# board_schematic.net
KiCad netlist of a schematic drawn in Altium Designer
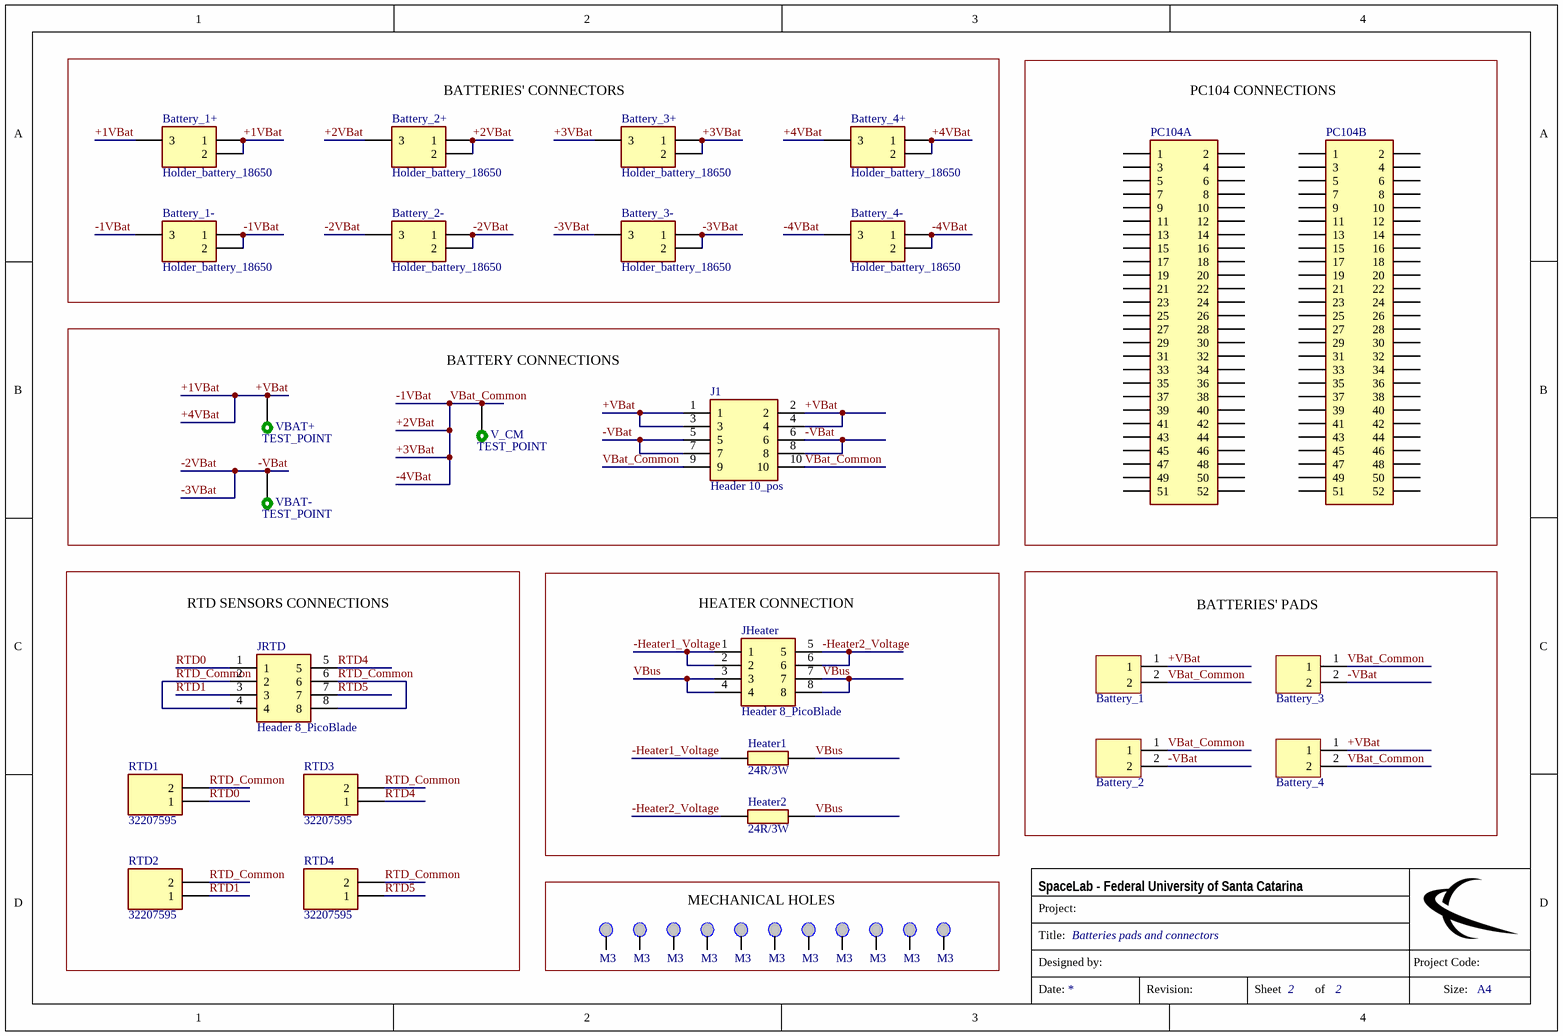
[diagram p0: board_schematic.schdoc]

(export (version "E")
  (design (tool "Eeschema 10.0.6"))
  (components
    (comp (ref "Battery_1")
      (value "BATTERY")
      (footprint "BATTERY")
      (description "Battery Pads")
      (libsource (lib "Battery_V2") (part "BATTERY"))
    )
    (comp (ref "Battery_1+")
      (value "Holder_battery_18650")
      (footprint "54")
      (description "Cylindrical Battery Contacts, Clips, Holders & Springs 16-19mm PC BATTERY CLIP")
      (fields (field (name "MANUFACTURER_PART_NUMBER") "54") (field (name "MOUSER PART NUMBER") "534-54"))
      (libsource (lib "*") (part "54"))
    )
    (comp (ref "Battery_1-")
      (value "Holder_battery_18650")
      (footprint "54")
      (description "Cylindrical Battery Contacts, Clips, Holders & Springs 16-19mm PC BATTERY CLIP")
      (fields (field (name "MANUFACTURER_PART_NUMBER") "54") (field (name "MOUSER PART NUMBER") "534-54"))
      (libsource (lib "*") (part "54"))
    )
    (comp (ref "Battery_2")
      (value "BATTERY")
      (footprint "BATTERY")
      (description "Battery Pads")
      (libsource (lib "Battery_V2") (part "BATTERY"))
    )
    (comp (ref "Battery_2+")
      (value "Holder_battery_18650")
      (footprint "54")
      (description "Cylindrical Battery Contacts, Clips, Holders & Springs 16-19mm PC BATTERY CLIP")
      (fields (field (name "MANUFACTURER_PART_NUMBER") "54") (field (name "MOUSER PART NUMBER") "534-54"))
      (libsource (lib "*") (part "54"))
    )
    (comp (ref "Battery_2-")
      (value "Holder_battery_18650")
      (footprint "54")
      (description "Cylindrical Battery Contacts, Clips, Holders & Springs 16-19mm PC BATTERY CLIP")
      (fields (field (name "MANUFACTURER_PART_NUMBER") "54") (field (name "MOUSER PART NUMBER") "534-54"))
      (libsource (lib "*") (part "54"))
    )
    (comp (ref "Battery_3")
      (value "BATTERY")
      (footprint "BATTERY")
      (description "Battery Pads")
      (libsource (lib "Battery_V2") (part "BATTERY"))
    )
    (comp (ref "Battery_3+")
      (value "Holder_battery_18650")
      (footprint "54")
      (description "Cylindrical Battery Contacts, Clips, Holders & Springs 16-19mm PC BATTERY CLIP")
      (fields (field (name "MANUFACTURER_PART_NUMBER") "54") (field (name "MOUSER PART NUMBER") "534-54"))
      (libsource (lib "*") (part "54"))
    )
    (comp (ref "Battery_3-")
      (value "Holder_battery_18650")
      (footprint "54")
      (description "Cylindrical Battery Contacts, Clips, Holders & Springs 16-19mm PC BATTERY CLIP")
      (fields (field (name "MANUFACTURER_PART_NUMBER") "54") (field (name "MOUSER PART NUMBER") "534-54"))
      (libsource (lib "*") (part "54"))
    )
    (comp (ref "Battery_4")
      (value "BATTERY")
      (footprint "BATTERY")
      (description "Battery Pads")
      (libsource (lib "Battery_V2") (part "BATTERY"))
    )
    (comp (ref "Battery_4+")
      (value "Holder_battery_18650")
      (footprint "54")
      (description "Cylindrical Battery Contacts, Clips, Holders & Springs 16-19mm PC BATTERY CLIP")
      (fields (field (name "MANUFACTURER_PART_NUMBER") "54") (field (name "MOUSER PART NUMBER") "534-54"))
      (libsource (lib "*") (part "54"))
    )
    (comp (ref "Battery_4-")
      (value "Holder_battery_18650")
      (footprint "54")
      (description "Cylindrical Battery Contacts, Clips, Holders & Springs 16-19mm PC BATTERY CLIP")
      (fields (field (name "MANUFACTURER_PART_NUMBER") "54") (field (name "MOUSER PART NUMBER") "534-54"))
      (libsource (lib "*") (part "54"))
    )
    (comp (ref "H1")
      (value "M3")
      (footprint "M3 hole")
      (description "M3 hole")
      (libsource (lib "Battery_V2") (part "M3 hole"))
    )
    (comp (ref "H2")
      (value "M3")
      (footprint "M3 hole")
      (description "M3 hole")
      (libsource (lib "Battery_V2") (part "M3 hole"))
    )
    (comp (ref "H3")
      (value "M3")
      (footprint "M3 hole")
      (description "M3 hole")
      (libsource (lib "Battery_V2") (part "M3 hole"))
    )
    (comp (ref "H4")
      (value "M3")
      (footprint "M3 hole")
      (description "M3 hole")
      (libsource (lib "Battery_V2") (part "M3 hole"))
    )
    (comp (ref "H5")
      (value "M3")
      (footprint "M3 hole")
      (description "M3 hole")
      (libsource (lib "Battery_V2") (part "M3 hole"))
    )
    (comp (ref "H6")
      (value "M3")
      (footprint "M3 hole")
      (description "M3 hole")
      (libsource (lib "Battery_V2") (part "M3 hole"))
    )
    (comp (ref "H7")
      (value "M3")
      (footprint "M3 hole")
      (description "M3 hole")
      (libsource (lib "Battery_V2") (part "M3 hole"))
    )
    (comp (ref "H8")
      (value "M3")
      (footprint "M3 hole")
      (description "M3 hole")
      (libsource (lib "Battery_V2") (part "M3 hole"))
    )
    (comp (ref "H9")
      (value "M3")
      (footprint "M3 hole")
      (description "M3 hole")
      (libsource (lib "Battery_V2") (part "M3 hole"))
    )
    (comp (ref "H10")
      (value "M3")
      (footprint "M3 hole")
      (description "M3 hole")
      (libsource (lib "Battery_V2") (part "M3 hole"))
    )
    (comp (ref "H11")
      (value "M3")
      (footprint "M3 hole")
      (description "M3 hole")
      (libsource (lib "Battery_V2") (part "M3 hole"))
    )
    (comp (ref "Heater1")
      (value "24R/3W")
      (footprint "RESAD3322W86L1422D475")
      (description "Wirewound Resistors - Through Hole 3watts 24ohms 1%")
      (fields (field (name "MANUFACTURER_PART_NUMBER") "RS02B24R00FE12"))
      (libsource (lib "*") (part "RS02B24R00FE12"))
    )
    (comp (ref "Heater2")
      (value "24R/3W")
      (footprint "RESAD3322W86L1422D475")
      (description "Wirewound Resistors - Through Hole 3watts 24ohms 1%")
      (fields (field (name "MANUFACTURER_PART_NUMBER") "RS02B24R00FE12"))
      (libsource (lib "*") (part "RS02B24R00FE12"))
    )
    (comp (ref "J1")
      (value "Header 10_pos")
      (footprint "Battery_V2:HDRV10W64P254_2X5_1270X502X521P")
      (description "Connector")
      (fields
        (field (name "MANUFACTURER_PART_NUMBER") "67996-110HLF")
        (field (name "MOUSER PART NUMBER") "649-67996-110HLF")
      )
      (libsource (lib "Battery_V2") (part "67996-110HLF"))
    )
    (comp (ref "JHeater")
      (value "Header 8_PicoBlade")
      (footprint "532610871")
      (description "Connector Header Surface Mount, Right Angle 8 position 0.049\" (1.25mm)")
      (fields
        (field (name "MANUFACTURER_PART_NUMBER") "53398-0871")
        (field (name "MOUSER PART NUMBER") "538-53398-0871")
      )
      (libsource (lib "schematics_library_legacy") (part "53261-0871"))
    )
    (comp (ref "JRTD")
      (value "Header 8_PicoBlade")
      (footprint "532610871")
      (description "Connector Header Surface Mount, Right Angle 8 position 0.049\" (1.25mm)")
      (fields
        (field (name "MANUFACTURER_PART_NUMBER") "53398-0871")
        (field (name "MOUSER PART NUMBER") "538-53398-0871")
      )
      (libsource (lib "schematics_library_legacy") (part "53261-0871"))
    )
    (comp (ref "PC104A")
      (value "ESQ-126-39-G-D")
      (footprint "ESQ-126-Y-X-D")
      (description "PC / 104 Connectors .100\" PC/104 Elevated Socket Strip")
      (fields (field (name "MOUSER PART NUMBER") "200-ESQ12639GD") (field (name "RS PART NUMBER") "1595654"))
      (libsource (lib "*") (part "ESQ-126-39-G-D"))
    )
    (comp (ref "PC104B")
      (value "ESQ-126-39-G-D")
      (footprint "ESQ-126-Y-X-D")
      (description "PC / 104 Connectors .100\" PC/104 Elevated Socket Strip")
      (fields (field (name "MOUSER PART NUMBER") "200-ESQ12639GD") (field (name "RS PART NUMBER") "1595654"))
      (libsource (lib "*") (part "ESQ-126-39-G-D"))
    )
    (comp (ref "RTD1")
      (value "32207595")
      (footprint "THRMC3216X70N")
      (description "Board Mount Temperature Sensors SMD1206(V) Pt 1000 Class B -50 to +130C")
      (libsource (lib "*") (part "32207595"))
    )
    (comp (ref "RTD2")
      (value "32207595")
      (footprint "THRMC3216X70N")
      (description "Board Mount Temperature Sensors SMD1206(V) Pt 1000 Class B -50 to +130C")
      (libsource (lib "*") (part "32207595"))
    )
    (comp (ref "RTD3")
      (value "32207595")
      (footprint "THRMC3216X70N")
      (description "Board Mount Temperature Sensors SMD1206(V) Pt 1000 Class B -50 to +130C")
      (libsource (lib "*") (part "32207595"))
    )
    (comp (ref "RTD4")
      (value "32207595")
      (footprint "THRMC3216X70N")
      (description "Board Mount Temperature Sensors SMD1206(V) Pt 1000 Class B -50 to +130C")
      (libsource (lib "*") (part "32207595"))
    )
    (comp (ref "VBAT+")
      (value "TEST_POINT")
      (footprint "Test_Point")
      (description "Test Point - Headers & Wire Housings .100\" Terminal Strip")
      (libsource (lib "Battery_V2") (part "TEST_POINT"))
    )
    (comp (ref "VBAT-")
      (value "TEST_POINT")
      (footprint "Test_Point")
      (description "Test Point - Headers & Wire Housings .100\" Terminal Strip")
      (libsource (lib "Battery_V2") (part "TEST_POINT"))
    )
    (comp (ref "V_CM")
      (value "TEST_POINT")
      (footprint "Test_Point")
      (description "Test Point - Headers & Wire Housings .100\" Terminal Strip")
      (libsource (lib "Battery_V2") (part "TEST_POINT"))
    )
  )
  (nets
    (net (code "1") (name "/+1VBat") (class "Default")
      (node (ref "Battery_1") (pin "1") (pinfunction "1_1") (pintype "passive"))
      (node (ref "Battery_1+") (pin "1") (pinfunction "1_1") (pintype "passive"))
      (node (ref "Battery_1+") (pin "2") (pinfunction "2_2") (pintype "passive"))
      (node (ref "Battery_1+") (pin "3") (pinfunction "3_3") (pintype "passive"))
      (node (ref "Battery_4") (pin "1") (pinfunction "1_1") (pintype "passive"))
      (node (ref "Battery_4+") (pin "1") (pinfunction "1_1") (pintype "passive"))
      (node (ref "Battery_4+") (pin "2") (pinfunction "2_2") (pintype "passive"))
      (node (ref "Battery_4+") (pin "3") (pinfunction "3_3") (pintype "passive"))
      (node (ref "J1") (pin "1") (pinfunction "1_1") (pintype "passive"))
      (node (ref "J1") (pin "2") (pinfunction "2_2") (pintype "passive"))
      (node (ref "J1") (pin "3") (pinfunction "3_3") (pintype "passive"))
      (node (ref "J1") (pin "4") (pinfunction "4_4") (pintype "passive"))
      (node (ref "VBAT+") (pin "1") (pinfunction "1_1") (pintype "passive"))
    )
    (net (code "2") (name "/+2VBat") (class "Default")
      (node (ref "Battery_1") (pin "2") (pinfunction "2_2") (pintype "passive"))
      (node (ref "Battery_1-") (pin "1") (pinfunction "1_1") (pintype "passive"))
      (node (ref "Battery_1-") (pin "2") (pinfunction "2_2") (pintype "passive"))
      (node (ref "Battery_1-") (pin "3") (pinfunction "3_3") (pintype "passive"))
      (node (ref "Battery_2") (pin "1") (pinfunction "1_1") (pintype "passive"))
      (node (ref "Battery_2+") (pin "1") (pinfunction "1_1") (pintype "passive"))
      (node (ref "Battery_2+") (pin "2") (pinfunction "2_2") (pintype "passive"))
      (node (ref "Battery_2+") (pin "3") (pinfunction "3_3") (pintype "passive"))
      (node (ref "Battery_3") (pin "1") (pinfunction "1_1") (pintype "passive"))
      (node (ref "Battery_3+") (pin "1") (pinfunction "1_1") (pintype "passive"))
      (node (ref "Battery_3+") (pin "2") (pinfunction "2_2") (pintype "passive"))
      (node (ref "Battery_3+") (pin "3") (pinfunction "3_3") (pintype "passive"))
      (node (ref "Battery_4") (pin "2") (pinfunction "2_2") (pintype "passive"))
      (node (ref "Battery_4-") (pin "1") (pinfunction "1_1") (pintype "passive"))
      (node (ref "Battery_4-") (pin "2") (pinfunction "2_2") (pintype "passive"))
      (node (ref "Battery_4-") (pin "3") (pinfunction "3_3") (pintype "passive"))
      (node (ref "J1") (pin "10") (pinfunction "10_10") (pintype "passive"))
      (node (ref "J1") (pin "9") (pinfunction "9_9") (pintype "passive"))
      (node (ref "V_CM") (pin "1") (pinfunction "1_1") (pintype "passive"))
    )
    (net (code "3") (name "/-2VBat") (class "Default")
      (node (ref "Battery_2") (pin "2") (pinfunction "2_2") (pintype "passive"))
      (node (ref "Battery_2-") (pin "1") (pinfunction "1_1") (pintype "passive"))
      (node (ref "Battery_2-") (pin "2") (pinfunction "2_2") (pintype "passive"))
      (node (ref "Battery_2-") (pin "3") (pinfunction "3_3") (pintype "passive"))
      (node (ref "Battery_3") (pin "2") (pinfunction "2_2") (pintype "passive"))
      (node (ref "Battery_3-") (pin "1") (pinfunction "1_1") (pintype "passive"))
      (node (ref "Battery_3-") (pin "2") (pinfunction "2_2") (pintype "passive"))
      (node (ref "Battery_3-") (pin "3") (pinfunction "3_3") (pintype "passive"))
      (node (ref "J1") (pin "5") (pinfunction "5_5") (pintype "passive"))
      (node (ref "J1") (pin "6") (pinfunction "6_6") (pintype "passive"))
      (node (ref "J1") (pin "7") (pinfunction "7_7") (pintype "passive"))
      (node (ref "J1") (pin "8") (pinfunction "8_8") (pintype "passive"))
      (node (ref "VBAT-") (pin "1") (pinfunction "1_1") (pintype "passive"))
    )
    (net (code "4") (name "/-Heater1_Voltage") (class "Default")
      (node (ref "Heater1") (pin "1") (pinfunction "1_1") (pintype "passive"))
      (node (ref "JHeater") (pin "1") (pinfunction "1_1") (pintype "passive"))
      (node (ref "JHeater") (pin "2") (pinfunction "2_2") (pintype "passive"))
    )
    (net (code "5") (name "/-Heater2_Voltage") (class "Default")
      (node (ref "Heater2") (pin "1") (pinfunction "1_1") (pintype "passive"))
      (node (ref "JHeater") (pin "5") (pinfunction "5_5") (pintype "passive"))
      (node (ref "JHeater") (pin "6") (pinfunction "6_6") (pintype "passive"))
    )
    (net (code "6") (name "/RTD0") (class "Default")
      (node (ref "JRTD") (pin "1") (pinfunction "1_1") (pintype "passive"))
      (node (ref "RTD1") (pin "1") (pinfunction "1_1") (pintype "passive"))
    )
    (net (code "7") (name "/RTD1") (class "Default")
      (node (ref "JRTD") (pin "3") (pinfunction "3_3") (pintype "passive"))
      (node (ref "RTD2") (pin "1") (pinfunction "1_1") (pintype "passive"))
    )
    (net (code "8") (name "/RTD4") (class "Default")
      (node (ref "JRTD") (pin "5") (pinfunction "5_5") (pintype "passive"))
      (node (ref "RTD3") (pin "1") (pinfunction "1_1") (pintype "passive"))
    )
    (net (code "9") (name "/RTD5") (class "Default")
      (node (ref "JRTD") (pin "7") (pinfunction "7_7") (pintype "passive"))
      (node (ref "RTD4") (pin "1") (pinfunction "1_1") (pintype "passive"))
    )
    (net (code "10") (name "/RTD_Common") (class "Default")
      (node (ref "JRTD") (pin "2") (pinfunction "2_2") (pintype "passive"))
      (node (ref "JRTD") (pin "4") (pinfunction "4_4") (pintype "passive"))
      (node (ref "JRTD") (pin "6") (pinfunction "6_6") (pintype "passive"))
      (node (ref "JRTD") (pin "8") (pinfunction "8_8") (pintype "passive"))
      (node (ref "RTD1") (pin "2") (pinfunction "2_2") (pintype "passive"))
      (node (ref "RTD2") (pin "2") (pinfunction "2_2") (pintype "passive"))
      (node (ref "RTD3") (pin "2") (pinfunction "2_2") (pintype "passive"))
      (node (ref "RTD4") (pin "2") (pinfunction "2_2") (pintype "passive"))
    )
    (net (code "11") (name "/VBus") (class "Default")
      (node (ref "Heater1") (pin "2") (pinfunction "2_2") (pintype "passive"))
      (node (ref "Heater2") (pin "2") (pinfunction "2_2") (pintype "passive"))
      (node (ref "JHeater") (pin "3") (pinfunction "3_3") (pintype "passive"))
      (node (ref "JHeater") (pin "4") (pinfunction "4_4") (pintype "passive"))
      (node (ref "JHeater") (pin "7") (pinfunction "7_7") (pintype "passive"))
      (node (ref "JHeater") (pin "8") (pinfunction "8_8") (pintype "passive"))
    )
    (net (code "12") (name "unconnected-(H1-Pad0)") (class "Default")
      (node (ref "H1") (pin "0") (pinfunction "0_0") (pintype "passive"))
    )
    (net (code "13") (name "unconnected-(H2-Pad0)") (class "Default")
      (node (ref "H2") (pin "0") (pinfunction "0_0") (pintype "passive"))
    )
    (net (code "14") (name "unconnected-(H3-Pad0)") (class "Default")
      (node (ref "H3") (pin "0") (pinfunction "0_0") (pintype "passive"))
    )
    (net (code "15") (name "unconnected-(H4-Pad0)") (class "Default")
      (node (ref "H4") (pin "0") (pinfunction "0_0") (pintype "passive"))
    )
    (net (code "16") (name "unconnected-(H5-Pad0)") (class "Default")
      (node (ref "H5") (pin "0") (pinfunction "0_0") (pintype "passive"))
    )
    (net (code "17") (name "unconnected-(H6-Pad0)") (class "Default")
      (node (ref "H6") (pin "0") (pinfunction "0_0") (pintype "passive"))
    )
    (net (code "18") (name "unconnected-(H7-Pad0)") (class "Default")
      (node (ref "H7") (pin "0") (pinfunction "0_0") (pintype "passive"))
    )
    (net (code "19") (name "unconnected-(H8-Pad0)") (class "Default")
      (node (ref "H8") (pin "0") (pinfunction "0_0") (pintype "passive"))
    )
    (net (code "20") (name "unconnected-(H9-Pad0)") (class "Default")
      (node (ref "H9") (pin "0") (pinfunction "0_0") (pintype "passive"))
    )
    (net (code "21") (name "unconnected-(H10-Pad0)") (class "Default")
      (node (ref "H10") (pin "0") (pinfunction "0_0") (pintype "passive"))
    )
    (net (code "22") (name "unconnected-(H11-Pad0)") (class "Default")
      (node (ref "H11") (pin "0") (pinfunction "0_0") (pintype "passive"))
    )
    (net (code "23") (name "unconnected-(PC104A-Pad1)") (class "Default")
      (node (ref "PC104A") (pin "1") (pinfunction "1_1") (pintype "passive"))
    )
    (net (code "24") (name "unconnected-(PC104A-Pad2)") (class "Default")
      (node (ref "PC104A") (pin "2") (pinfunction "2_2") (pintype "passive"))
    )
    (net (code "25") (name "unconnected-(PC104A-Pad3)") (class "Default")
      (node (ref "PC104A") (pin "3") (pinfunction "3_3") (pintype "passive"))
    )
    (net (code "26") (name "unconnected-(PC104A-Pad4)") (class "Default")
      (node (ref "PC104A") (pin "4") (pinfunction "4_4") (pintype "passive"))
    )
    (net (code "27") (name "unconnected-(PC104A-Pad5)") (class "Default")
      (node (ref "PC104A") (pin "5") (pinfunction "5_5") (pintype "passive"))
    )
    (net (code "28") (name "unconnected-(PC104A-Pad6)") (class "Default")
      (node (ref "PC104A") (pin "6") (pinfunction "6_6") (pintype "passive"))
    )
    (net (code "29") (name "unconnected-(PC104A-Pad7)") (class "Default")
      (node (ref "PC104A") (pin "7") (pinfunction "7_7") (pintype "passive"))
    )
    (net (code "30") (name "unconnected-(PC104A-Pad8)") (class "Default")
      (node (ref "PC104A") (pin "8") (pinfunction "8_8") (pintype "passive"))
    )
    (net (code "31") (name "unconnected-(PC104A-Pad9)") (class "Default")
      (node (ref "PC104A") (pin "9") (pinfunction "9_9") (pintype "passive"))
    )
    (net (code "32") (name "unconnected-(PC104A-Pad10)") (class "Default")
      (node (ref "PC104A") (pin "10") (pinfunction "10_10") (pintype "passive"))
    )
    (net (code "33") (name "unconnected-(PC104A-Pad11)") (class "Default")
      (node (ref "PC104A") (pin "11") (pinfunction "11_11") (pintype "passive"))
    )
    (net (code "34") (name "unconnected-(PC104A-Pad12)") (class "Default")
      (node (ref "PC104A") (pin "12") (pinfunction "12_12") (pintype "passive"))
    )
    (net (code "35") (name "unconnected-(PC104A-Pad13)") (class "Default")
      (node (ref "PC104A") (pin "13") (pinfunction "13_13") (pintype "passive"))
    )
    (net (code "36") (name "unconnected-(PC104A-Pad14)") (class "Default")
      (node (ref "PC104A") (pin "14") (pinfunction "14_14") (pintype "passive"))
    )
    (net (code "37") (name "unconnected-(PC104A-Pad15)") (class "Default")
      (node (ref "PC104A") (pin "15") (pinfunction "15_15") (pintype "passive"))
    )
    (net (code "38") (name "unconnected-(PC104A-Pad16)") (class "Default")
      (node (ref "PC104A") (pin "16") (pinfunction "16_16") (pintype "passive"))
    )
    (net (code "39") (name "unconnected-(PC104A-Pad17)") (class "Default")
      (node (ref "PC104A") (pin "17") (pinfunction "17_17") (pintype "passive"))
    )
    (net (code "40") (name "unconnected-(PC104A-Pad18)") (class "Default")
      (node (ref "PC104A") (pin "18") (pinfunction "18_18") (pintype "passive"))
    )
    (net (code "41") (name "unconnected-(PC104A-Pad19)") (class "Default")
      (node (ref "PC104A") (pin "19") (pinfunction "19_19") (pintype "passive"))
    )
    (net (code "42") (name "unconnected-(PC104A-Pad20)") (class "Default")
      (node (ref "PC104A") (pin "20") (pinfunction "20_20") (pintype "passive"))
    )
    (net (code "43") (name "unconnected-(PC104A-Pad21)") (class "Default")
      (node (ref "PC104A") (pin "21") (pinfunction "21_21") (pintype "passive"))
    )
    (net (code "44") (name "unconnected-(PC104A-Pad22)") (class "Default")
      (node (ref "PC104A") (pin "22") (pinfunction "22_22") (pintype "passive"))
    )
    (net (code "45") (name "unconnected-(PC104A-Pad23)") (class "Default")
      (node (ref "PC104A") (pin "23") (pinfunction "23_23") (pintype "passive"))
    )
    (net (code "46") (name "unconnected-(PC104A-Pad24)") (class "Default")
      (node (ref "PC104A") (pin "24") (pinfunction "24_24") (pintype "passive"))
    )
    (net (code "47") (name "unconnected-(PC104A-Pad25)") (class "Default")
      (node (ref "PC104A") (pin "25") (pinfunction "25_25") (pintype "passive"))
    )
    (net (code "48") (name "unconnected-(PC104A-Pad26)") (class "Default")
      (node (ref "PC104A") (pin "26") (pinfunction "26_26") (pintype "passive"))
    )
    (net (code "49") (name "unconnected-(PC104A-Pad27)") (class "Default")
      (node (ref "PC104A") (pin "27") (pinfunction "27_27") (pintype "passive"))
    )
    (net (code "50") (name "unconnected-(PC104A-Pad28)") (class "Default")
      (node (ref "PC104A") (pin "28") (pinfunction "28_28") (pintype "passive"))
    )
    (net (code "51") (name "unconnected-(PC104A-Pad29)") (class "Default")
      (node (ref "PC104A") (pin "29") (pinfunction "29_29") (pintype "passive"))
    )
    (net (code "52") (name "unconnected-(PC104A-Pad30)") (class "Default")
      (node (ref "PC104A") (pin "30") (pinfunction "30_30") (pintype "passive"))
    )
    (net (code "53") (name "unconnected-(PC104A-Pad31)") (class "Default")
      (node (ref "PC104A") (pin "31") (pinfunction "31_31") (pintype "passive"))
    )
    (net (code "54") (name "unconnected-(PC104A-Pad32)") (class "Default")
      (node (ref "PC104A") (pin "32") (pinfunction "32_32") (pintype "passive"))
    )
    (net (code "55") (name "unconnected-(PC104A-Pad33)") (class "Default")
      (node (ref "PC104A") (pin "33") (pinfunction "33_33") (pintype "passive"))
    )
    (net (code "56") (name "unconnected-(PC104A-Pad34)") (class "Default")
      (node (ref "PC104A") (pin "34") (pinfunction "34_34") (pintype "passive"))
    )
    (net (code "57") (name "unconnected-(PC104A-Pad35)") (class "Default")
      (node (ref "PC104A") (pin "35") (pinfunction "35_35") (pintype "passive"))
    )
    (net (code "58") (name "unconnected-(PC104A-Pad36)") (class "Default")
      (node (ref "PC104A") (pin "36") (pinfunction "36_36") (pintype "passive"))
    )
    (net (code "59") (name "unconnected-(PC104A-Pad37)") (class "Default")
      (node (ref "PC104A") (pin "37") (pinfunction "37_37") (pintype "passive"))
    )
    (net (code "60") (name "unconnected-(PC104A-Pad38)") (class "Default")
      (node (ref "PC104A") (pin "38") (pinfunction "38_38") (pintype "passive"))
    )
    (net (code "61") (name "unconnected-(PC104A-Pad39)") (class "Default")
      (node (ref "PC104A") (pin "39") (pinfunction "39_39") (pintype "passive"))
    )
    (net (code "62") (name "unconnected-(PC104A-Pad40)") (class "Default")
      (node (ref "PC104A") (pin "40") (pinfunction "40_40") (pintype "passive"))
    )
    (net (code "63") (name "unconnected-(PC104A-Pad41)") (class "Default")
      (node (ref "PC104A") (pin "41") (pinfunction "41_41") (pintype "passive"))
    )
    (net (code "64") (name "unconnected-(PC104A-Pad42)") (class "Default")
      (node (ref "PC104A") (pin "42") (pinfunction "42_42") (pintype "passive"))
    )
    (net (code "65") (name "unconnected-(PC104A-Pad43)") (class "Default")
      (node (ref "PC104A") (pin "43") (pinfunction "43_43") (pintype "passive"))
    )
    (net (code "66") (name "unconnected-(PC104A-Pad44)") (class "Default")
      (node (ref "PC104A") (pin "44") (pinfunction "44_44") (pintype "passive"))
    )
    (net (code "67") (name "unconnected-(PC104A-Pad45)") (class "Default")
      (node (ref "PC104A") (pin "45") (pinfunction "45_45") (pintype "passive"))
    )
    (net (code "68") (name "unconnected-(PC104A-Pad46)") (class "Default")
      (node (ref "PC104A") (pin "46") (pinfunction "46_46") (pintype "passive"))
    )
    (net (code "69") (name "unconnected-(PC104A-Pad47)") (class "Default")
      (node (ref "PC104A") (pin "47") (pinfunction "47_47") (pintype "passive"))
    )
    (net (code "70") (name "unconnected-(PC104A-Pad48)") (class "Default")
      (node (ref "PC104A") (pin "48") (pinfunction "48_48") (pintype "passive"))
    )
    (net (code "71") (name "unconnected-(PC104A-Pad49)") (class "Default")
      (node (ref "PC104A") (pin "49") (pinfunction "49_49") (pintype "passive"))
    )
    (net (code "72") (name "unconnected-(PC104A-Pad50)") (class "Default")
      (node (ref "PC104A") (pin "50") (pinfunction "50_50") (pintype "passive"))
    )
    (net (code "73") (name "unconnected-(PC104A-Pad51)") (class "Default")
      (node (ref "PC104A") (pin "51") (pinfunction "51_51") (pintype "passive"))
    )
    (net (code "74") (name "unconnected-(PC104A-Pad52)") (class "Default")
      (node (ref "PC104A") (pin "52") (pinfunction "52_52") (pintype "passive"))
    )
    (net (code "75") (name "unconnected-(PC104B-Pad1)") (class "Default")
      (node (ref "PC104B") (pin "1") (pinfunction "1_1") (pintype "passive"))
    )
    (net (code "76") (name "unconnected-(PC104B-Pad2)") (class "Default")
      (node (ref "PC104B") (pin "2") (pinfunction "2_2") (pintype "passive"))
    )
    (net (code "77") (name "unconnected-(PC104B-Pad3)") (class "Default")
      (node (ref "PC104B") (pin "3") (pinfunction "3_3") (pintype "passive"))
    )
    (net (code "78") (name "unconnected-(PC104B-Pad4)") (class "Default")
      (node (ref "PC104B") (pin "4") (pinfunction "4_4") (pintype "passive"))
    )
    (net (code "79") (name "unconnected-(PC104B-Pad5)") (class "Default")
      (node (ref "PC104B") (pin "5") (pinfunction "5_5") (pintype "passive"))
    )
    (net (code "80") (name "unconnected-(PC104B-Pad6)") (class "Default")
      (node (ref "PC104B") (pin "6") (pinfunction "6_6") (pintype "passive"))
    )
    (net (code "81") (name "unconnected-(PC104B-Pad7)") (class "Default")
      (node (ref "PC104B") (pin "7") (pinfunction "7_7") (pintype "passive"))
    )
    (net (code "82") (name "unconnected-(PC104B-Pad8)") (class "Default")
      (node (ref "PC104B") (pin "8") (pinfunction "8_8") (pintype "passive"))
    )
    (net (code "83") (name "unconnected-(PC104B-Pad9)") (class "Default")
      (node (ref "PC104B") (pin "9") (pinfunction "9_9") (pintype "passive"))
    )
    (net (code "84") (name "unconnected-(PC104B-Pad10)") (class "Default")
      (node (ref "PC104B") (pin "10") (pinfunction "10_10") (pintype "passive"))
    )
    (net (code "85") (name "unconnected-(PC104B-Pad11)") (class "Default")
      (node (ref "PC104B") (pin "11") (pinfunction "11_11") (pintype "passive"))
    )
    (net (code "86") (name "unconnected-(PC104B-Pad12)") (class "Default")
      (node (ref "PC104B") (pin "12") (pinfunction "12_12") (pintype "passive"))
    )
    (net (code "87") (name "unconnected-(PC104B-Pad13)") (class "Default")
      (node (ref "PC104B") (pin "13") (pinfunction "13_13") (pintype "passive"))
    )
    (net (code "88") (name "unconnected-(PC104B-Pad14)") (class "Default")
      (node (ref "PC104B") (pin "14") (pinfunction "14_14") (pintype "passive"))
    )
    (net (code "89") (name "unconnected-(PC104B-Pad15)") (class "Default")
      (node (ref "PC104B") (pin "15") (pinfunction "15_15") (pintype "passive"))
    )
    (net (code "90") (name "unconnected-(PC104B-Pad16)") (class "Default")
      (node (ref "PC104B") (pin "16") (pinfunction "16_16") (pintype "passive"))
    )
    (net (code "91") (name "unconnected-(PC104B-Pad17)") (class "Default")
      (node (ref "PC104B") (pin "17") (pinfunction "17_17") (pintype "passive"))
    )
    (net (code "92") (name "unconnected-(PC104B-Pad18)") (class "Default")
      (node (ref "PC104B") (pin "18") (pinfunction "18_18") (pintype "passive"))
    )
    (net (code "93") (name "unconnected-(PC104B-Pad19)") (class "Default")
      (node (ref "PC104B") (pin "19") (pinfunction "19_19") (pintype "passive"))
    )
    (net (code "94") (name "unconnected-(PC104B-Pad20)") (class "Default")
      (node (ref "PC104B") (pin "20") (pinfunction "20_20") (pintype "passive"))
    )
    (net (code "95") (name "unconnected-(PC104B-Pad21)") (class "Default")
      (node (ref "PC104B") (pin "21") (pinfunction "21_21") (pintype "passive"))
    )
    (net (code "96") (name "unconnected-(PC104B-Pad22)") (class "Default")
      (node (ref "PC104B") (pin "22") (pinfunction "22_22") (pintype "passive"))
    )
    (net (code "97") (name "unconnected-(PC104B-Pad23)") (class "Default")
      (node (ref "PC104B") (pin "23") (pinfunction "23_23") (pintype "passive"))
    )
    (net (code "98") (name "unconnected-(PC104B-Pad24)") (class "Default")
      (node (ref "PC104B") (pin "24") (pinfunction "24_24") (pintype "passive"))
    )
    (net (code "99") (name "unconnected-(PC104B-Pad25)") (class "Default")
      (node (ref "PC104B") (pin "25") (pinfunction "25_25") (pintype "passive"))
    )
    (net (code "100") (name "unconnected-(PC104B-Pad26)") (class "Default")
      (node (ref "PC104B") (pin "26") (pinfunction "26_26") (pintype "passive"))
    )
    (net (code "101") (name "unconnected-(PC104B-Pad27)") (class "Default")
      (node (ref "PC104B") (pin "27") (pinfunction "27_27") (pintype "passive"))
    )
    (net (code "102") (name "unconnected-(PC104B-Pad28)") (class "Default")
      (node (ref "PC104B") (pin "28") (pinfunction "28_28") (pintype "passive"))
    )
    (net (code "103") (name "unconnected-(PC104B-Pad29)") (class "Default")
      (node (ref "PC104B") (pin "29") (pinfunction "29_29") (pintype "passive"))
    )
    (net (code "104") (name "unconnected-(PC104B-Pad30)") (class "Default")
      (node (ref "PC104B") (pin "30") (pinfunction "30_30") (pintype "passive"))
    )
    (net (code "105") (name "unconnected-(PC104B-Pad31)") (class "Default")
      (node (ref "PC104B") (pin "31") (pinfunction "31_31") (pintype "passive"))
    )
    (net (code "106") (name "unconnected-(PC104B-Pad32)") (class "Default")
      (node (ref "PC104B") (pin "32") (pinfunction "32_32") (pintype "passive"))
    )
    (net (code "107") (name "unconnected-(PC104B-Pad33)") (class "Default")
      (node (ref "PC104B") (pin "33") (pinfunction "33_33") (pintype "passive"))
    )
    (net (code "108") (name "unconnected-(PC104B-Pad34)") (class "Default")
      (node (ref "PC104B") (pin "34") (pinfunction "34_34") (pintype "passive"))
    )
    (net (code "109") (name "unconnected-(PC104B-Pad35)") (class "Default")
      (node (ref "PC104B") (pin "35") (pinfunction "35_35") (pintype "passive"))
    )
    (net (code "110") (name "unconnected-(PC104B-Pad36)") (class "Default")
      (node (ref "PC104B") (pin "36") (pinfunction "36_36") (pintype "passive"))
    )
    (net (code "111") (name "unconnected-(PC104B-Pad37)") (class "Default")
      (node (ref "PC104B") (pin "37") (pinfunction "37_37") (pintype "passive"))
    )
    (net (code "112") (name "unconnected-(PC104B-Pad38)") (class "Default")
      (node (ref "PC104B") (pin "38") (pinfunction "38_38") (pintype "passive"))
    )
    (net (code "113") (name "unconnected-(PC104B-Pad39)") (class "Default")
      (node (ref "PC104B") (pin "39") (pinfunction "39_39") (pintype "passive"))
    )
    (net (code "114") (name "unconnected-(PC104B-Pad40)") (class "Default")
      (node (ref "PC104B") (pin "40") (pinfunction "40_40") (pintype "passive"))
    )
    (net (code "115") (name "unconnected-(PC104B-Pad41)") (class "Default")
      (node (ref "PC104B") (pin "41") (pinfunction "41_41") (pintype "passive"))
    )
    (net (code "116") (name "unconnected-(PC104B-Pad42)") (class "Default")
      (node (ref "PC104B") (pin "42") (pinfunction "42_42") (pintype "passive"))
    )
    (net (code "117") (name "unconnected-(PC104B-Pad43)") (class "Default")
      (node (ref "PC104B") (pin "43") (pinfunction "43_43") (pintype "passive"))
    )
    (net (code "118") (name "unconnected-(PC104B-Pad44)") (class "Default")
      (node (ref "PC104B") (pin "44") (pinfunction "44_44") (pintype "passive"))
    )
    (net (code "119") (name "unconnected-(PC104B-Pad45)") (class "Default")
      (node (ref "PC104B") (pin "45") (pinfunction "45_45") (pintype "passive"))
    )
    (net (code "120") (name "unconnected-(PC104B-Pad46)") (class "Default")
      (node (ref "PC104B") (pin "46") (pinfunction "46_46") (pintype "passive"))
    )
    (net (code "121") (name "unconnected-(PC104B-Pad47)") (class "Default")
      (node (ref "PC104B") (pin "47") (pinfunction "47_47") (pintype "passive"))
    )
    (net (code "122") (name "unconnected-(PC104B-Pad48)") (class "Default")
      (node (ref "PC104B") (pin "48") (pinfunction "48_48") (pintype "passive"))
    )
    (net (code "123") (name "unconnected-(PC104B-Pad49)") (class "Default")
      (node (ref "PC104B") (pin "49") (pinfunction "49_49") (pintype "passive"))
    )
    (net (code "124") (name "unconnected-(PC104B-Pad50)") (class "Default")
      (node (ref "PC104B") (pin "50") (pinfunction "50_50") (pintype "passive"))
    )
    (net (code "125") (name "unconnected-(PC104B-Pad51)") (class "Default")
      (node (ref "PC104B") (pin "51") (pinfunction "51_51") (pintype "passive"))
    )
    (net (code "126") (name "unconnected-(PC104B-Pad52)") (class "Default")
      (node (ref "PC104B") (pin "52") (pinfunction "52_52") (pintype "passive"))
    )
  )
)
